# RADG-USB-S04-V00.net
KiCad netlist of a schematic drawn in Altium Designer
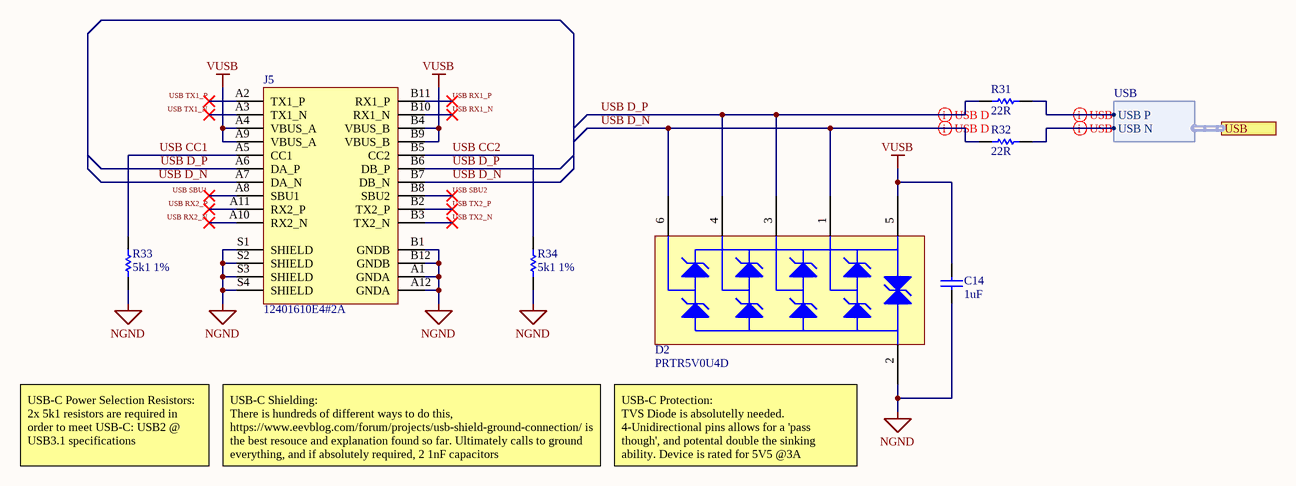
[diagram p0: RADG-USB-S04-V00.SchDoc]

(export (version "E")
  (design (tool "Eeschema 10.0.6"))
  (components
    (comp (ref "C14")
      (value "1uF")
      (footprint "Cap_Ceramic_0603")
      (description "Capacitor, Ceramic, SMD, 1uF, 25V, 5%, X7R, 0603")
      (libsource (lib "StandardCapacitors") (part "1uF 25V 5% X7R 0603"))
    )
    (comp (ref "D2")
      (value "PRTR5V0U4D")
      (footprint "SC-47")
      (description "Clamp Ipp Tvs Diode Surface Mount 6-TSOP")
      (libsource (lib "QUTMS_DiodeLibrary") (part "PRTR5V0U4D"))
    )
    (comp (ref "J5")
      (value "12401610E4#2A")
      (footprint "12401610E4#2A")
      (libsource (lib "QUTMS_USBLibrary") (part "12401610E4#2A"))
    )
    (comp (ref "R31")
      (value "22R")
      (footprint "Res_ThinFilm_0603")
      (description "Resistor, SMD, 22R, 0.1W, 5%, 0603")
      (libsource (lib "StandardResistors") (part "22R 5% 0603"))
    )
    (comp (ref "R32")
      (value "22R")
      (footprint "Res_ThinFilm_0603")
      (description "Resistor, SMD, 22R, 0.1W, 5%, 0603")
      (libsource (lib "StandardResistors") (part "22R 5% 0603"))
    )
    (comp (ref "R33")
      (value "5k1 1%")
      (footprint "Res_ThinFilm_0603")
      (description "Resistor, SMD, 5k1, 0.1W, 1%, 0603")
      (libsource (lib "StandardResistors") (part "5k1 1% 0603"))
    )
    (comp (ref "R34")
      (value "5k1 1%")
      (footprint "Res_ThinFilm_0603")
      (description "Resistor, SMD, 5k1, 0.1W, 1%, 0603")
      (libsource (lib "StandardResistors") (part "5k1 1% 0603"))
    )
  )
  (nets
    (net (code "2") (name "/USB CC1") (class "Default")
      (node (ref "J5") (pin "A5") (pinfunction "CC1_A5") (pintype "passive"))
      (node (ref "R33") (pin "2") (pinfunction "2_2") (pintype "passive"))
    )
    (net (code "3") (name "/USB CC2") (class "Default")
      (node (ref "J5") (pin "B5") (pinfunction "CC2_B5") (pintype "passive"))
      (node (ref "R34") (pin "2") (pinfunction "2_2") (pintype "passive"))
    )
    (net (code "4") (name "/USB D_N") (class "Default")
      (node (ref "D2") (pin "1") (pinfunction "P1_1") (pintype "passive"))
      (node (ref "D2") (pin "6") (pinfunction "P4_6") (pintype "passive"))
      (node (ref "J5") (pin "A7") (pinfunction "DA_N_A7") (pintype "passive"))
      (node (ref "J5") (pin "B7") (pinfunction "DB_N_B7") (pintype "passive"))
      (node (ref "R32") (pin "1") (pinfunction "1_1") (pintype "passive"))
    )
    (net (code "5") (name "/USB D_P") (class "Default")
      (node (ref "D2") (pin "3") (pinfunction "P2_3") (pintype "passive"))
      (node (ref "D2") (pin "4") (pinfunction "P3_4") (pintype "passive"))
      (node (ref "J5") (pin "A6") (pinfunction "DA_P_A6") (pintype "passive"))
      (node (ref "J5") (pin "B6") (pinfunction "DB_P_B6") (pintype "passive"))
      (node (ref "R31") (pin "1") (pinfunction "1_1") (pintype "passive"))
    )
    (net (code "6") (name "/USB N") (class "Default")
      (node (ref "R32") (pin "2") (pinfunction "2_2") (pintype "passive"))
    )
    (net (code "7") (name "/USB P") (class "Default")
      (node (ref "R31") (pin "2") (pinfunction "2_2") (pintype "passive"))
    )
    (net (code "8") (name "/USB RX1_N") (class "Default")
      (node (ref "J5") (pin "B10") (pinfunction "RX1_N_B10") (pintype "passive+no_connect"))
    )
    (net (code "9") (name "/USB RX1_P") (class "Default")
      (node (ref "J5") (pin "B11") (pinfunction "RX1_P_B11") (pintype "passive+no_connect"))
    )
    (net (code "10") (name "/USB RX2_N") (class "Default")
      (node (ref "J5") (pin "A10") (pinfunction "RX2_N_A10") (pintype "passive+no_connect"))
    )
    (net (code "11") (name "/USB RX2_P") (class "Default")
      (node (ref "J5") (pin "A11") (pinfunction "RX2_P_A11") (pintype "passive+no_connect"))
    )
    (net (code "12") (name "/USB SBU1") (class "Default")
      (node (ref "J5") (pin "A8") (pinfunction "SBU1_A8") (pintype "passive+no_connect"))
    )
    (net (code "13") (name "/USB SBU2") (class "Default")
      (node (ref "J5") (pin "B8") (pinfunction "SBU2_B8") (pintype "passive+no_connect"))
    )
    (net (code "14") (name "/USB TX1_N") (class "Default")
      (node (ref "J5") (pin "A3") (pinfunction "TX1_N_A3") (pintype "passive+no_connect"))
    )
    (net (code "15") (name "/USB TX1_P") (class "Default")
      (node (ref "J5") (pin "A2") (pinfunction "TX1_P_A2") (pintype "passive+no_connect"))
    )
    (net (code "16") (name "/USB TX2_N") (class "Default")
      (node (ref "J5") (pin "B3") (pinfunction "TX2_N_B3") (pintype "passive+no_connect"))
    )
    (net (code "17") (name "/USB TX2_P") (class "Default")
      (node (ref "J5") (pin "B2") (pinfunction "TX2_P_B2") (pintype "passive+no_connect"))
    )
    (net (code "19") (name "NGND") (class "Default")
      (node (ref "C14") (pin "1") (pinfunction "1_1") (pintype "passive"))
      (node (ref "D2") (pin "2") (pinfunction "GND_2") (pintype "passive"))
      (node (ref "J5") (pin "A1") (pinfunction "GNDA_A1") (pintype "passive"))
      (node (ref "J5") (pin "A12") (pinfunction "GNDA_A12") (pintype "passive"))
      (node (ref "J5") (pin "B1") (pinfunction "GNDB_B1") (pintype "passive"))
      (node (ref "J5") (pin "B12") (pinfunction "GNDB_B12") (pintype "passive"))
      (node (ref "J5") (pin "S1") (pinfunction "SHIELD_S1") (pintype "power_in"))
      (node (ref "J5") (pin "S2") (pinfunction "SHIELD_S2") (pintype "power_in"))
      (node (ref "J5") (pin "S3") (pinfunction "SHIELD_S3") (pintype "power_in"))
      (node (ref "J5") (pin "S4") (pinfunction "SHIELD_S4") (pintype "power_in"))
      (node (ref "R33") (pin "1") (pinfunction "1_1") (pintype "passive"))
      (node (ref "R34") (pin "1") (pinfunction "1_1") (pintype "passive"))
    )
    (net (code "20") (name "VUSB") (class "Default")
      (node (ref "C14") (pin "2") (pinfunction "2_2") (pintype "passive"))
      (node (ref "D2") (pin "5") (pinfunction "VCC_5") (pintype "passive"))
      (node (ref "J5") (pin "A4") (pinfunction "VBUS_A_A4") (pintype "passive"))
      (node (ref "J5") (pin "A9") (pinfunction "VBUS_A_A9") (pintype "passive"))
      (node (ref "J5") (pin "B4") (pinfunction "VBUS_B_B4") (pintype "passive"))
      (node (ref "J5") (pin "B9") (pinfunction "VBUS_B_B9") (pintype "passive"))
    )
  )
)
